# 2_MXM_Connector_1.net
KiCad netlist of a schematic drawn in Altium Designer
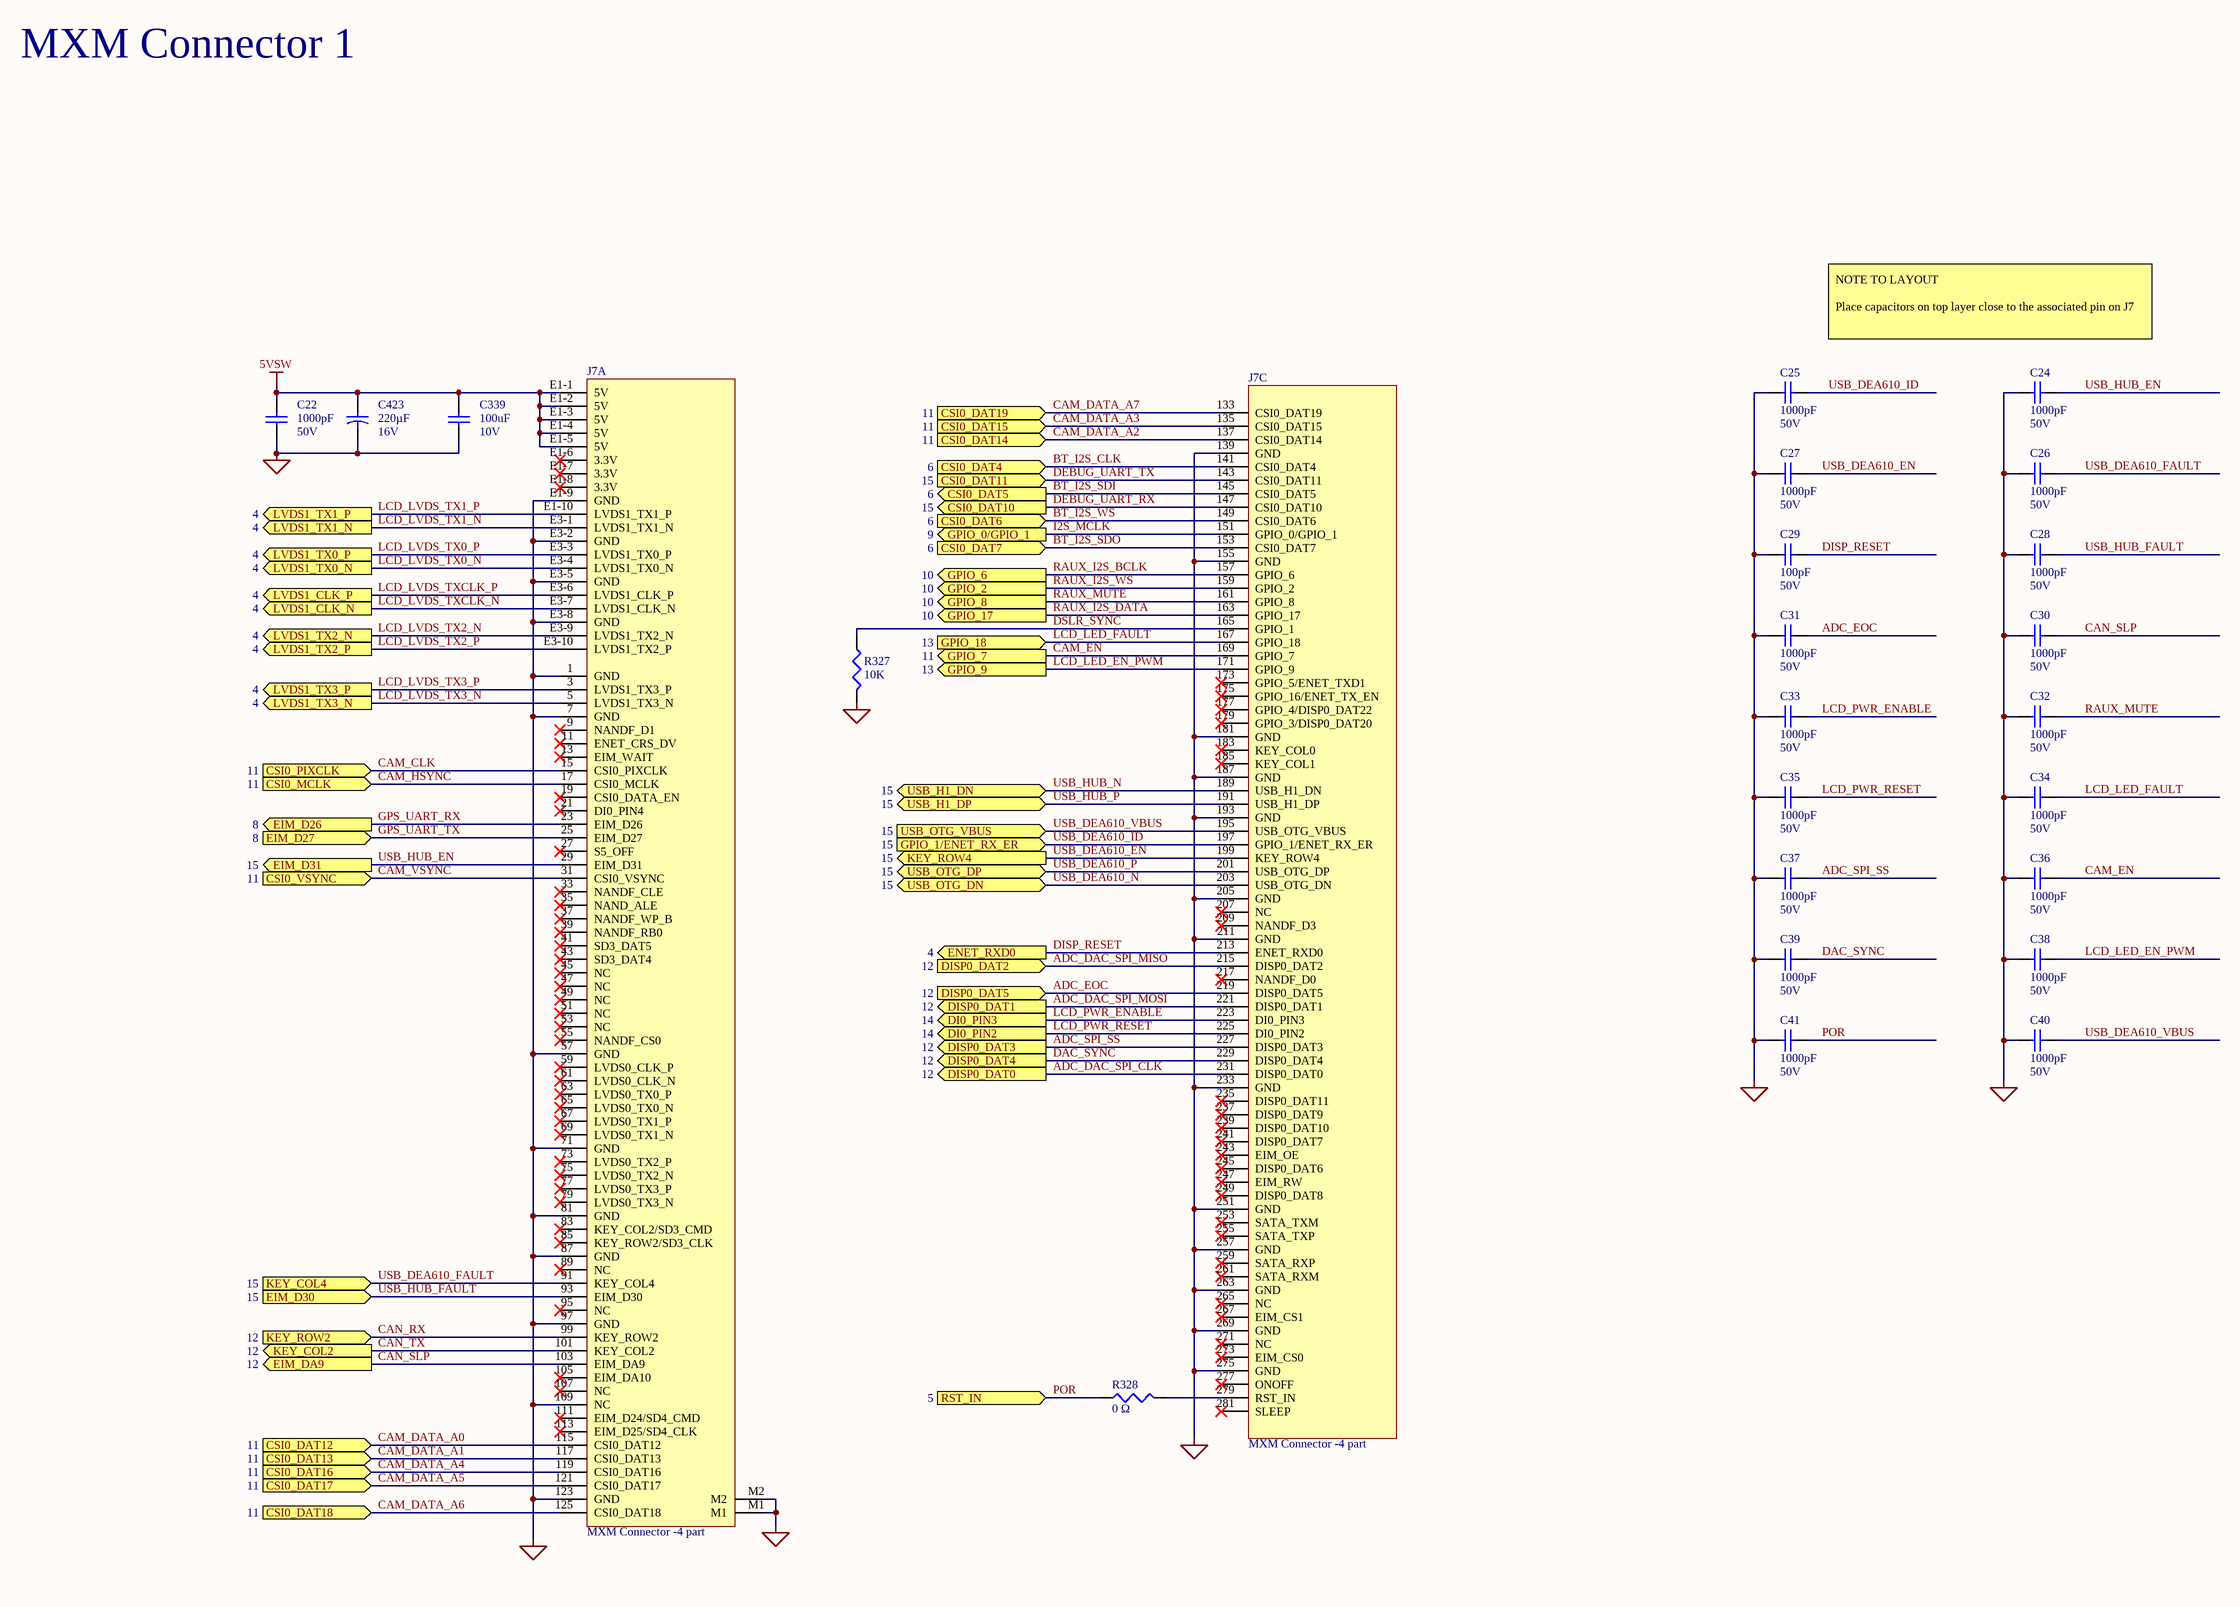
[diagram p0: 2 MXM Connector 1.SchDoc]

(export (version "E")
  (design (tool "Eeschema 10.0.6"))
  (components
    (comp (ref "C22")
      (value "1000pF")
      (footprint "CAP_0402")
      (description "Cap, Cer, 1000pF, 50V, 20%, X7R, 0402")
      (fields
        (field (name "TOLERANCE") "20%")
        (field (name "MANUFACTURER") "Murata Electronics North America")
        (field (name "VOLTAGE") "50V")
      )
      (libsource (lib "Firstview") (part "Cap 1000pF 50V 0402"))
    )
    (comp (ref "C24")
      (value "1000pF")
      (footprint "CAP_0402")
      (description "Cap, Cer, 1000pF, 50V, 20%, X7R, 0402")
      (fields
        (field (name "TOLERANCE") "20%")
        (field (name "MANUFACTURER") "Murata Electronics North America")
        (field (name "VOLTAGE") "50V")
      )
      (libsource (lib "Firstview") (part "Cap 1000pF 50V 0402"))
    )
    (comp (ref "C25")
      (value "1000pF")
      (footprint "CAP_0402")
      (description "Cap, Cer, 1000pF, 50V, 20%, X7R, 0402")
      (fields
        (field (name "TOLERANCE") "20%")
        (field (name "MANUFACTURER") "Murata Electronics North America")
        (field (name "VOLTAGE") "50V")
      )
      (libsource (lib "Firstview") (part "Cap 1000pF 50V 0402"))
    )
    (comp (ref "C26")
      (value "1000pF")
      (footprint "CAP_0402")
      (description "Cap, Cer, 1000pF, 50V, 20%, X7R, 0402")
      (fields
        (field (name "TOLERANCE") "20%")
        (field (name "MANUFACTURER") "Murata Electronics North America")
        (field (name "VOLTAGE") "50V")
      )
      (libsource (lib "Firstview") (part "Cap 1000pF 50V 0402"))
    )
    (comp (ref "C27")
      (value "1000pF")
      (footprint "CAP_0402")
      (description "Cap, Cer, 1000pF, 50V, 20%, X7R, 0402")
      (fields
        (field (name "TOLERANCE") "20%")
        (field (name "MANUFACTURER") "Murata Electronics North America")
        (field (name "VOLTAGE") "50V")
      )
      (libsource (lib "Firstview") (part "Cap 1000pF 50V 0402"))
    )
    (comp (ref "C28")
      (value "1000pF")
      (footprint "CAP_0402")
      (description "Cap, Cer, 1000pF, 50V, 20%, X7R, 0402")
      (fields
        (field (name "TOLERANCE") "20%")
        (field (name "MANUFACTURER") "Murata Electronics North America")
        (field (name "VOLTAGE") "50V")
      )
      (libsource (lib "Firstview") (part "Cap 1000pF 50V 0402"))
    )
    (comp (ref "C29")
      (value "100pF")
      (footprint "CAP_0402")
      (description "Cap, Cer, 100pF, 50V, 5%, C0G/NP0, 0402")
      (fields
        (field (name "TOLERANCE") "5%")
        (field (name "MANUFACTURER") "Yageo")
        (field (name "VOLTAGE") "50V")
      )
      (libsource (lib "Firstview") (part "Cap 100pF 50V 0402"))
    )
    (comp (ref "C30")
      (value "1000pF")
      (footprint "CAP_0402")
      (description "Cap, Cer, 1000pF, 50V, 20%, X7R, 0402")
      (fields
        (field (name "TOLERANCE") "20%")
        (field (name "MANUFACTURER") "Murata Electronics North America")
        (field (name "VOLTAGE") "50V")
      )
      (libsource (lib "Firstview") (part "Cap 1000pF 50V 0402"))
    )
    (comp (ref "C31")
      (value "1000pF")
      (footprint "CAP_0402")
      (description "Cap, Cer, 1000pF, 50V, 20%, X7R, 0402")
      (fields
        (field (name "TOLERANCE") "20%")
        (field (name "MANUFACTURER") "Murata Electronics North America")
        (field (name "VOLTAGE") "50V")
      )
      (libsource (lib "Firstview") (part "Cap 1000pF 50V 0402"))
    )
    (comp (ref "C32")
      (value "1000pF")
      (footprint "CAP_0402")
      (description "Cap, Cer, 1000pF, 50V, 20%, X7R, 0402")
      (fields
        (field (name "TOLERANCE") "20%")
        (field (name "MANUFACTURER") "Murata Electronics North America")
        (field (name "VOLTAGE") "50V")
      )
      (libsource (lib "Firstview") (part "Cap 1000pF 50V 0402"))
    )
    (comp (ref "C33")
      (value "1000pF")
      (footprint "CAP_0402")
      (description "Cap, Cer, 1000pF, 50V, 20%, X7R, 0402")
      (fields
        (field (name "TOLERANCE") "20%")
        (field (name "MANUFACTURER") "Murata Electronics North America")
        (field (name "VOLTAGE") "50V")
      )
      (libsource (lib "Firstview") (part "Cap 1000pF 50V 0402"))
    )
    (comp (ref "C34")
      (value "1000pF")
      (footprint "CAP_0402")
      (description "Cap, Cer, 1000pF, 50V, 20%, X7R, 0402")
      (fields
        (field (name "TOLERANCE") "20%")
        (field (name "MANUFACTURER") "Murata Electronics North America")
        (field (name "VOLTAGE") "50V")
      )
      (libsource (lib "Firstview") (part "Cap 1000pF 50V 0402"))
    )
    (comp (ref "C35")
      (value "1000pF")
      (footprint "CAP_0402")
      (description "Cap, Cer, 1000pF, 50V, 20%, X7R, 0402")
      (fields
        (field (name "TOLERANCE") "20%")
        (field (name "MANUFACTURER") "Murata Electronics North America")
        (field (name "VOLTAGE") "50V")
      )
      (libsource (lib "Firstview") (part "Cap 1000pF 50V 0402"))
    )
    (comp (ref "C36")
      (value "1000pF")
      (footprint "CAP_0402")
      (description "Cap, Cer, 1000pF, 50V, 20%, X7R, 0402")
      (fields
        (field (name "TOLERANCE") "20%")
        (field (name "MANUFACTURER") "Murata Electronics North America")
        (field (name "VOLTAGE") "50V")
      )
      (libsource (lib "Firstview") (part "Cap 1000pF 50V 0402"))
    )
    (comp (ref "C37")
      (value "1000pF")
      (footprint "CAP_0402")
      (description "Cap, Cer, 1000pF, 50V, 20%, X7R, 0402")
      (fields
        (field (name "TOLERANCE") "20%")
        (field (name "MANUFACTURER") "Murata Electronics North America")
        (field (name "VOLTAGE") "50V")
      )
      (libsource (lib "Firstview") (part "Cap 1000pF 50V 0402"))
    )
    (comp (ref "C38")
      (value "1000pF")
      (footprint "CAP_0402")
      (description "Cap, Cer, 1000pF, 50V, 20%, X7R, 0402")
      (fields
        (field (name "TOLERANCE") "20%")
        (field (name "MANUFACTURER") "Murata Electronics North America")
        (field (name "VOLTAGE") "50V")
      )
      (libsource (lib "Firstview") (part "Cap 1000pF 50V 0402"))
    )
    (comp (ref "C39")
      (value "1000pF")
      (footprint "CAP_0402")
      (description "Cap, Cer, 1000pF, 50V, 20%, X7R, 0402")
      (fields
        (field (name "TOLERANCE") "20%")
        (field (name "MANUFACTURER") "Murata Electronics North America")
        (field (name "VOLTAGE") "50V")
      )
      (libsource (lib "Firstview") (part "Cap 1000pF 50V 0402"))
    )
    (comp (ref "C40")
      (value "1000pF")
      (footprint "CAP_0402")
      (description "Cap, Cer, 1000pF, 50V, 20%, X7R, 0402")
      (fields
        (field (name "TOLERANCE") "20%")
        (field (name "MANUFACTURER") "Murata Electronics North America")
        (field (name "VOLTAGE") "50V")
      )
      (libsource (lib "Firstview") (part "Cap 1000pF 50V 0402"))
    )
    (comp (ref "C41")
      (value "1000pF")
      (footprint "CAP_0402")
      (description "Cap, Cer, 1000pF, 50V, 20%, X7R, 0402")
      (fields
        (field (name "TOLERANCE") "20%")
        (field (name "MANUFACTURER") "Murata Electronics North America")
        (field (name "VOLTAGE") "50V")
      )
      (libsource (lib "Firstview") (part "Cap 1000pF 50V 0402"))
    )
    (comp (ref "C339")
      (value "100uF")
      (footprint "CAP_1210")
      (description "Cap, Cer, 100uF, 10V, 20%, X5R, 1210")
      (fields
        (field (name "MANUFACTURER") "Kemet")
        (field (name "VOLTAGE") "10V")
        (field (name "Comment") "Cap 100uF 10V 1210")
      )
      (libsource (lib "Firstview") (part "Cap 100uF 10V 1210"))
    )
    (comp (ref "C423")
      (value "220µF")
      (footprint "SMD(6.6x6.6)_UWT1C221MCL1GS")
      (description "Cap, Alum, 220µF, 16V, 20%, SMD")
      (fields
        (field (name "TOLERANCE") "20%")
        (field (name "MANUFACTURER") "Nichicon")
        (field (name "VOLTAGE") "16V")
      )
      (libsource (lib "Firstview") (part "Cap 220µF 16V"))
    )
    (comp (ref "J7")
      (value "MXM Connector -4 part")
      (footprint "CON_CLE9990-0402F")
      (description "Conn, 314-pin, SOM i.MX6, SMD")
      (fields (field (name "MANUFACTURER") "SMK Electronics"))
      (libsource (lib "Firstview") (part "MXM Connector -4 part"))
    )
    (comp (ref "R327")
      (value "10K")
      (footprint "RES_0402")
      (description "Res, 10K, 1/16W, 1%, 0402")
      (fields (field (name "MANUFACTURER") "Yageo") (field (name "Comment") "Res 10K 0.063W"))
      (libsource (lib "Firstview") (part "Res 10K 0.063W"))
    )
    (comp (ref "R328")
      (value "0 Ω")
      (footprint "RES_0402")
      (description "Res, 0 ohm, 1/16W, 0402")
      (fields (field (name "MANUFACTURER") "Vishay Dale") (field (name "Comment") "Res 0 ohm 0.1W"))
      (libsource (lib "Firstview") (part "Res 0 ohm 0.1W"))
    )
  )
  (nets
    (net (code "1") (name "/ADC_DAC_SPI_CLK") (class "Default")
      (node (ref "J7") (pin "231") (pinfunction "DISP0_DAT0_231") (pintype "passive"))
    )
    (net (code "2") (name "/ADC_DAC_SPI_MISO") (class "Default")
      (node (ref "J7") (pin "215") (pinfunction "DISP0_DAT2_215") (pintype "passive"))
    )
    (net (code "3") (name "/ADC_DAC_SPI_MOSI") (class "Default")
      (node (ref "J7") (pin "221") (pinfunction "DISP0_DAT1_221") (pintype "passive"))
    )
    (net (code "4") (name "/ADC_EOC") (class "Default")
      (node (ref "C31") (pin "1") (pinfunction "1_1") (pintype "passive"))
      (node (ref "J7") (pin "219") (pinfunction "DISP0_DAT5_219") (pintype "passive"))
    )
    (net (code "5") (name "/ADC_SPI_SS") (class "Default")
      (node (ref "C37") (pin "1") (pinfunction "1_1") (pintype "passive"))
      (node (ref "J7") (pin "227") (pinfunction "DISP0_DAT3_227") (pintype "passive"))
    )
    (net (code "6") (name "/BT_I2S_CLK") (class "Default")
      (node (ref "J7") (pin "141") (pinfunction "CSI0_DAT4_141") (pintype "passive"))
    )
    (net (code "7") (name "/BT_I2S_SDI") (class "Default")
      (node (ref "J7") (pin "145") (pinfunction "CSI0_DAT5_145") (pintype "passive"))
    )
    (net (code "8") (name "/BT_I2S_SDO") (class "Default")
      (node (ref "J7") (pin "153") (pinfunction "CSI0_DAT7_153") (pintype "passive"))
    )
    (net (code "9") (name "/BT_I2S_WS") (class "Default")
      (node (ref "J7") (pin "149") (pinfunction "CSI0_DAT6_149") (pintype "passive"))
    )
    (net (code "10") (name "/CAM_CLK") (class "Default")
      (node (ref "J7") (pin "15") (pinfunction "CSI0_PIXCLK_15") (pintype "passive"))
    )
    (net (code "11") (name "/CAM_DATA_A0") (class "Default")
      (node (ref "J7") (pin "115") (pinfunction "CSI0_DAT12_115") (pintype "passive"))
    )
    (net (code "12") (name "/CAM_DATA_A1") (class "Default")
      (node (ref "J7") (pin "117") (pinfunction "CSI0_DAT13_117") (pintype "passive"))
    )
    (net (code "13") (name "/CAM_DATA_A2") (class "Default")
      (node (ref "J7") (pin "137") (pinfunction "CSI0_DAT14_137") (pintype "passive"))
    )
    (net (code "14") (name "/CAM_DATA_A3") (class "Default")
      (node (ref "J7") (pin "135") (pinfunction "CSI0_DAT15_135") (pintype "passive"))
    )
    (net (code "15") (name "/CAM_DATA_A4") (class "Default")
      (node (ref "J7") (pin "119") (pinfunction "CSI0_DAT16_119") (pintype "passive"))
    )
    (net (code "16") (name "/CAM_DATA_A5") (class "Default")
      (node (ref "J7") (pin "121") (pinfunction "CSI0_DAT17_121") (pintype "passive"))
    )
    (net (code "17") (name "/CAM_DATA_A6") (class "Default")
      (node (ref "J7") (pin "125") (pinfunction "CSI0_DAT18_125") (pintype "passive"))
    )
    (net (code "18") (name "/CAM_DATA_A7") (class "Default")
      (node (ref "J7") (pin "133") (pinfunction "CSI0_DAT19_133") (pintype "passive"))
    )
    (net (code "19") (name "/CAM_EN") (class "Default")
      (node (ref "C36") (pin "1") (pinfunction "1_1") (pintype "passive"))
      (node (ref "J7") (pin "169") (pinfunction "GPIO_7_169") (pintype "passive"))
    )
    (net (code "20") (name "/CAM_HSYNC") (class "Default")
      (node (ref "J7") (pin "17") (pinfunction "CSI0_MCLK_17") (pintype "passive"))
    )
    (net (code "21") (name "/CAM_VSYNC") (class "Default")
      (node (ref "J7") (pin "31") (pinfunction "CSI0_VSYNC_31") (pintype "passive"))
    )
    (net (code "22") (name "/CAN_RX") (class "Default")
      (node (ref "J7") (pin "99") (pinfunction "KEY_ROW2_99") (pintype "passive"))
    )
    (net (code "23") (name "/CAN_SLP") (class "Default")
      (node (ref "C30") (pin "1") (pinfunction "1_1") (pintype "passive"))
      (node (ref "J7") (pin "103") (pinfunction "EIM_DA9_103") (pintype "passive"))
    )
    (net (code "24") (name "/CAN_TX") (class "Default")
      (node (ref "J7") (pin "101") (pinfunction "KEY_COL2_101") (pintype "passive"))
    )
    (net (code "25") (name "/DAC_SYNC") (class "Default")
      (node (ref "C39") (pin "1") (pinfunction "1_1") (pintype "passive"))
      (node (ref "J7") (pin "229") (pinfunction "DISP0_DAT4_229") (pintype "passive"))
    )
    (net (code "26") (name "/DEBUG_UART_RX") (class "Default")
      (node (ref "J7") (pin "147") (pinfunction "CSI0_DAT10_147") (pintype "passive"))
    )
    (net (code "27") (name "/DEBUG_UART_TX") (class "Default")
      (node (ref "J7") (pin "143") (pinfunction "CSI0_DAT11_143") (pintype "passive"))
    )
    (net (code "28") (name "/DISP_RESET") (class "Default")
      (node (ref "C29") (pin "1") (pinfunction "1_1") (pintype "passive"))
      (node (ref "J7") (pin "213") (pinfunction "ENET_RXD0_213") (pintype "passive"))
    )
    (net (code "29") (name "/DSLR_SYNC") (class "Default")
      (node (ref "J7") (pin "165") (pinfunction "GPIO_1_165") (pintype "passive"))
      (node (ref "R327") (pin "1") (pinfunction "1_1") (pintype "passive"))
    )
    (net (code "30") (name "/GPS_UART_RX") (class "Default")
      (node (ref "J7") (pin "23") (pinfunction "EIM_D26_23") (pintype "passive"))
    )
    (net (code "31") (name "/GPS_UART_TX") (class "Default")
      (node (ref "J7") (pin "25") (pinfunction "EIM_D27_25") (pintype "passive"))
    )
    (net (code "32") (name "/I2S_MCLK") (class "Default")
      (node (ref "J7") (pin "151") (pinfunction "GPIO_0/GPIO_1_151") (pintype "passive"))
    )
    (net (code "33") (name "/LCD_LED_EN_PWM") (class "Default")
      (node (ref "C38") (pin "1") (pinfunction "1_1") (pintype "passive"))
      (node (ref "J7") (pin "171") (pinfunction "GPIO_9_171") (pintype "passive"))
    )
    (net (code "34") (name "/LCD_LED_FAULT") (class "Default")
      (node (ref "C34") (pin "1") (pinfunction "1_1") (pintype "passive"))
      (node (ref "J7") (pin "167") (pinfunction "GPIO_18_167") (pintype "passive"))
    )
    (net (code "35") (name "/LCD_LVDS_TX0_N") (class "Default")
      (node (ref "J7") (pin "E3-4") (pinfunction "LVDS1_TX0_N_E3-4") (pintype "passive"))
    )
    (net (code "36") (name "/LCD_LVDS_TX0_P") (class "Default")
      (node (ref "J7") (pin "E3-3") (pinfunction "LVDS1_TX0_P_E3-3") (pintype "passive"))
    )
    (net (code "37") (name "/LCD_LVDS_TX1_N") (class "Default")
      (node (ref "J7") (pin "E3-1") (pinfunction "LVDS1_TX1_N_E3-1") (pintype "passive"))
    )
    (net (code "38") (name "/LCD_LVDS_TX1_P") (class "Default")
      (node (ref "J7") (pin "E1-10") (pinfunction "LVDS1_TX1_P_E1-10") (pintype "passive"))
    )
    (net (code "39") (name "/LCD_LVDS_TX2_N") (class "Default")
      (node (ref "J7") (pin "E3-9") (pinfunction "LVDS1_TX2_N_E3-9") (pintype "passive"))
    )
    (net (code "40") (name "/LCD_LVDS_TX2_P") (class "Default")
      (node (ref "J7") (pin "E3-10") (pinfunction "LVDS1_TX2_P_E3-10") (pintype "passive"))
    )
    (net (code "41") (name "/LCD_LVDS_TX3_N") (class "Default")
      (node (ref "J7") (pin "5") (pinfunction "LVDS1_TX3_N_5") (pintype "passive"))
    )
    (net (code "42") (name "/LCD_LVDS_TX3_P") (class "Default")
      (node (ref "J7") (pin "3") (pinfunction "LVDS1_TX3_P_3") (pintype "passive"))
    )
    (net (code "43") (name "/LCD_LVDS_TXCLK_N") (class "Default")
      (node (ref "J7") (pin "E3-7") (pinfunction "LVDS1_CLK_N_E3-7") (pintype "passive"))
    )
    (net (code "44") (name "/LCD_LVDS_TXCLK_P") (class "Default")
      (node (ref "J7") (pin "E3-6") (pinfunction "LVDS1_CLK_P_E3-6") (pintype "passive"))
    )
    (net (code "45") (name "/LCD_PWR_ENABLE") (class "Default")
      (node (ref "C33") (pin "1") (pinfunction "1_1") (pintype "passive"))
      (node (ref "J7") (pin "223") (pinfunction "DI0_PIN3_223") (pintype "passive"))
    )
    (net (code "46") (name "/LCD_PWR_RESET") (class "Default")
      (node (ref "C35") (pin "1") (pinfunction "1_1") (pintype "passive"))
      (node (ref "J7") (pin "225") (pinfunction "DI0_PIN2_225") (pintype "passive"))
    )
    (net (code "47") (name "/POR") (class "Default")
      (node (ref "C41") (pin "1") (pinfunction "1_1") (pintype "passive"))
      (node (ref "R328") (pin "1") (pinfunction "1_1") (pintype "passive"))
    )
    (net (code "48") (name "/RAUX_I2S_BCLK") (class "Default")
      (node (ref "J7") (pin "157") (pinfunction "GPIO_6_157") (pintype "passive"))
    )
    (net (code "49") (name "/RAUX_I2S_DATA") (class "Default")
      (node (ref "J7") (pin "163") (pinfunction "GPIO_17_163") (pintype "passive"))
    )
    (net (code "50") (name "/RAUX_I2S_WS") (class "Default")
      (node (ref "J7") (pin "159") (pinfunction "GPIO_2_159") (pintype "passive"))
    )
    (net (code "51") (name "/RAUX_MUTE") (class "Default")
      (node (ref "C32") (pin "1") (pinfunction "1_1") (pintype "passive"))
      (node (ref "J7") (pin "161") (pinfunction "GPIO_8_161") (pintype "passive"))
    )
    (net (code "52") (name "/USB_DEA610_EN") (class "Default")
      (node (ref "C27") (pin "1") (pinfunction "1_1") (pintype "passive"))
      (node (ref "J7") (pin "199") (pinfunction "KEY_ROW4_199") (pintype "passive"))
    )
    (net (code "53") (name "/USB_DEA610_FAULT") (class "Default")
      (node (ref "C26") (pin "1") (pinfunction "1_1") (pintype "passive"))
      (node (ref "J7") (pin "91") (pinfunction "KEY_COL4_91") (pintype "passive"))
    )
    (net (code "54") (name "/USB_DEA610_ID") (class "Default")
      (node (ref "C25") (pin "1") (pinfunction "1_1") (pintype "passive"))
      (node (ref "J7") (pin "197") (pinfunction "GPIO_1/ENET_RX_ER_197") (pintype "passive"))
    )
    (net (code "55") (name "/USB_DEA610_N") (class "Default")
      (node (ref "J7") (pin "203") (pinfunction "USB_OTG_DN_203") (pintype "passive"))
    )
    (net (code "56") (name "/USB_DEA610_P") (class "Default")
      (node (ref "J7") (pin "201") (pinfunction "USB_OTG_DP_201") (pintype "passive"))
    )
    (net (code "57") (name "/USB_DEA610_VBUS") (class "Default")
      (node (ref "C40") (pin "1") (pinfunction "1_1") (pintype "passive"))
      (node (ref "J7") (pin "195") (pinfunction "USB_OTG_VBUS_195") (pintype "passive"))
    )
    (net (code "58") (name "/USB_HUB_EN") (class "Default")
      (node (ref "C24") (pin "1") (pinfunction "1_1") (pintype "passive"))
      (node (ref "J7") (pin "29") (pinfunction "EIM_D31_29") (pintype "passive"))
    )
    (net (code "59") (name "/USB_HUB_FAULT") (class "Default")
      (node (ref "C28") (pin "1") (pinfunction "1_1") (pintype "passive"))
      (node (ref "J7") (pin "93") (pinfunction "EIM_D30_93") (pintype "passive"))
    )
    (net (code "60") (name "/USB_HUB_N") (class "Default")
      (node (ref "J7") (pin "189") (pinfunction "USB_H1_DN_189") (pintype "passive"))
    )
    (net (code "61") (name "/USB_HUB_P") (class "Default")
      (node (ref "J7") (pin "191") (pinfunction "USB_H1_DP_191") (pintype "passive"))
    )
    (net (code "62") (name "5VSW") (class "Default")
      (node (ref "C22") (pin "1") (pinfunction "1_1") (pintype "passive"))
      (node (ref "C339") (pin "1") (pinfunction "1_1") (pintype "passive"))
      (node (ref "C423") (pin "1") (pinfunction "1_1") (pintype "passive"))
      (node (ref "J7") (pin "E1-1") (pinfunction "5V_E1-1") (pintype "passive"))
      (node (ref "J7") (pin "E1-2") (pinfunction "5V_E1-2") (pintype "passive"))
      (node (ref "J7") (pin "E1-3") (pinfunction "5V_E1-3") (pintype "passive"))
      (node (ref "J7") (pin "E1-4") (pinfunction "5V_E1-4") (pintype "passive"))
      (node (ref "J7") (pin "E1-5") (pinfunction "5V_E1-5") (pintype "passive"))
    )
    (net (code "63") (name "GND") (class "Default")
      (node (ref "C22") (pin "2") (pinfunction "2_2") (pintype "passive"))
      (node (ref "C24") (pin "2") (pinfunction "2_2") (pintype "passive"))
      (node (ref "C25") (pin "2") (pinfunction "2_2") (pintype "passive"))
      (node (ref "C26") (pin "2") (pinfunction "2_2") (pintype "passive"))
      (node (ref "C27") (pin "2") (pinfunction "2_2") (pintype "passive"))
      (node (ref "C28") (pin "2") (pinfunction "2_2") (pintype "passive"))
      (node (ref "C29") (pin "2") (pinfunction "2_2") (pintype "passive"))
      (node (ref "C30") (pin "2") (pinfunction "2_2") (pintype "passive"))
      (node (ref "C31") (pin "2") (pinfunction "2_2") (pintype "passive"))
      (node (ref "C32") (pin "2") (pinfunction "2_2") (pintype "passive"))
      (node (ref "C33") (pin "2") (pinfunction "2_2") (pintype "passive"))
      (node (ref "C339") (pin "2") (pinfunction "2_2") (pintype "passive"))
      (node (ref "C34") (pin "2") (pinfunction "2_2") (pintype "passive"))
      (node (ref "C35") (pin "2") (pinfunction "2_2") (pintype "passive"))
      (node (ref "C36") (pin "2") (pinfunction "2_2") (pintype "passive"))
      (node (ref "C37") (pin "2") (pinfunction "2_2") (pintype "passive"))
      (node (ref "C38") (pin "2") (pinfunction "2_2") (pintype "passive"))
      (node (ref "C39") (pin "2") (pinfunction "2_2") (pintype "passive"))
      (node (ref "C40") (pin "2") (pinfunction "2_2") (pintype "passive"))
      (node (ref "C41") (pin "2") (pinfunction "2_2") (pintype "passive"))
      (node (ref "C423") (pin "2") (pinfunction "2_2") (pintype "passive"))
      (node (ref "J7") (pin "1") (pinfunction "GND_1") (pintype "passive"))
      (node (ref "J7") (pin "109") (pinfunction "NC_109") (pintype "passive"))
      (node (ref "J7") (pin "123") (pinfunction "GND_123") (pintype "passive"))
      (node (ref "J7") (pin "139") (pinfunction "GND_139") (pintype "passive"))
      (node (ref "J7") (pin "155") (pinfunction "GND_155") (pintype "passive"))
      (node (ref "J7") (pin "181") (pinfunction "GND_181") (pintype "passive"))
      (node (ref "J7") (pin "187") (pinfunction "GND_187") (pintype "passive"))
      (node (ref "J7") (pin "193") (pinfunction "GND_193") (pintype "passive"))
      (node (ref "J7") (pin "205") (pinfunction "GND_205") (pintype "passive"))
      (node (ref "J7") (pin "211") (pinfunction "GND_211") (pintype "passive"))
      (node (ref "J7") (pin "233") (pinfunction "GND_233") (pintype "passive"))
      (node (ref "J7") (pin "251") (pinfunction "GND_251") (pintype "passive"))
      (node (ref "J7") (pin "257") (pinfunction "GND_257") (pintype "passive"))
      (node (ref "J7") (pin "263") (pinfunction "GND_263") (pintype "passive"))
      (node (ref "J7") (pin "269") (pinfunction "GND_269") (pintype "passive"))
      (node (ref "J7") (pin "275") (pinfunction "GND_275") (pintype "passive"))
      (node (ref "J7") (pin "57") (pinfunction "GND_57") (pintype "passive"))
      (node (ref "J7") (pin "7") (pinfunction "GND_7") (pintype "passive"))
      (node (ref "J7") (pin "71") (pinfunction "GND_71") (pintype "passive"))
      (node (ref "J7") (pin "81") (pinfunction "GND_81") (pintype "passive"))
      (node (ref "J7") (pin "87") (pinfunction "GND_87") (pintype "passive"))
      (node (ref "J7") (pin "97") (pinfunction "GND_97") (pintype "passive"))
      (node (ref "J7") (pin "E1-9") (pinfunction "GND_E1-9") (pintype "passive"))
      (node (ref "J7") (pin "E3-2") (pinfunction "GND_E3-2") (pintype "passive"))
      (node (ref "J7") (pin "E3-5") (pinfunction "GND_E3-5") (pintype "passive"))
      (node (ref "J7") (pin "E3-8") (pinfunction "GND_E3-8") (pintype "passive"))
      (node (ref "J7") (pin "M1") (pinfunction "M1_M1") (pintype "passive"))
      (node (ref "J7") (pin "M2") (pinfunction "M2_M2") (pintype "passive"))
      (node (ref "R327") (pin "2") (pinfunction "2_2") (pintype "passive"))
    )
    (net (code "64") (name "Net-(J7C-RST_IN)") (class "Default")
      (node (ref "J7") (pin "279") (pinfunction "RST_IN_279") (pintype "passive"))
      (node (ref "R328") (pin "2") (pinfunction "2_2") (pintype "passive"))
    )
    (net (code "65") (name "unconnected-(J7A-3.3V-PadE1-6)") (class "Default")
      (node (ref "J7") (pin "E1-6") (pinfunction "3.3V_E1-6") (pintype "passive+no_connect"))
    )
    (net (code "66") (name "unconnected-(J7A-3.3V-PadE1-7)") (class "Default")
      (node (ref "J7") (pin "E1-7") (pinfunction "3.3V_E1-7") (pintype "passive+no_connect"))
    )
    (net (code "67") (name "unconnected-(J7A-3.3V-PadE1-8)") (class "Default")
      (node (ref "J7") (pin "E1-8") (pinfunction "3.3V_E1-8") (pintype "passive+no_connect"))
    )
    (net (code "68") (name "unconnected-(J7A-CSI0_DATA_EN-Pad19)") (class "Default")
      (node (ref "J7") (pin "19") (pinfunction "CSI0_DATA_EN_19") (pintype "passive+no_connect"))
    )
    (net (code "69") (name "unconnected-(J7A-DI0_PIN4-Pad21)") (class "Default")
      (node (ref "J7") (pin "21") (pinfunction "DI0_PIN4_21") (pintype "passive+no_connect"))
    )
    (net (code "70") (name "unconnected-(J7A-EIM_D24{slash}SD4_CMD-Pad111)") (class "Default")
      (node (ref "J7") (pin "111") (pinfunction "EIM_D24/SD4_CMD_111") (pintype "passive+no_connect"))
    )
    (net (code "71") (name "unconnected-(J7A-EIM_D25{slash}SD4_CLK-Pad113)") (class "Default")
      (node (ref "J7") (pin "113") (pinfunction "EIM_D25/SD4_CLK_113") (pintype "passive+no_connect"))
    )
    (net (code "72") (name "unconnected-(J7A-EIM_DA10-Pad105)") (class "Default")
      (node (ref "J7") (pin "105") (pinfunction "EIM_DA10_105") (pintype "passive+no_connect"))
    )
    (net (code "73") (name "unconnected-(J7A-EIM_WAIT-Pad13)") (class "Default")
      (node (ref "J7") (pin "13") (pinfunction "EIM_WAIT_13") (pintype "passive+no_connect"))
    )
    (net (code "74") (name "unconnected-(J7A-ENET_CRS_DV-Pad11)") (class "Default")
      (node (ref "J7") (pin "11") (pinfunction "ENET_CRS_DV_11") (pintype "passive+no_connect"))
    )
    (net (code "75") (name "unconnected-(J7A-KEY_COL2{slash}SD3_CMD-Pad83)") (class "Default")
      (node (ref "J7") (pin "83") (pinfunction "KEY_COL2/SD3_CMD_83") (pintype "passive+no_connect"))
    )
    (net (code "76") (name "unconnected-(J7A-KEY_ROW2{slash}SD3_CLK-Pad85)") (class "Default")
      (node (ref "J7") (pin "85") (pinfunction "KEY_ROW2/SD3_CLK_85") (pintype "passive+no_connect"))
    )
    (net (code "77") (name "unconnected-(J7A-LVDS0_CLK_N-Pad61)") (class "Default")
      (node (ref "J7") (pin "61") (pinfunction "LVDS0_CLK_N_61") (pintype "passive+no_connect"))
    )
    (net (code "78") (name "unconnected-(J7A-LVDS0_CLK_P-Pad59)") (class "Default")
      (node (ref "J7") (pin "59") (pinfunction "LVDS0_CLK_P_59") (pintype "passive+no_connect"))
    )
    (net (code "79") (name "unconnected-(J7A-LVDS0_TX0_N-Pad65)") (class "Default")
      (node (ref "J7") (pin "65") (pinfunction "LVDS0_TX0_N_65") (pintype "passive+no_connect"))
    )
    (net (code "80") (name "unconnected-(J7A-LVDS0_TX0_P-Pad63)") (class "Default")
      (node (ref "J7") (pin "63") (pinfunction "LVDS0_TX0_P_63") (pintype "passive+no_connect"))
    )
    (net (code "81") (name "unconnected-(J7A-LVDS0_TX1_N-Pad69)") (class "Default")
      (node (ref "J7") (pin "69") (pinfunction "LVDS0_TX1_N_69") (pintype "passive+no_connect"))
    )
    (net (code "82") (name "unconnected-(J7A-LVDS0_TX1_P-Pad67)") (class "Default")
      (node (ref "J7") (pin "67") (pinfunction "LVDS0_TX1_P_67") (pintype "passive+no_connect"))
    )
    (net (code "83") (name "unconnected-(J7A-LVDS0_TX2_N-Pad75)") (class "Default")
      (node (ref "J7") (pin "75") (pinfunction "LVDS0_TX2_N_75") (pintype "passive+no_connect"))
    )
    (net (code "84") (name "unconnected-(J7A-LVDS0_TX2_P-Pad73)") (class "Default")
      (node (ref "J7") (pin "73") (pinfunction "LVDS0_TX2_P_73") (pintype "passive+no_connect"))
    )
    (net (code "85") (name "unconnected-(J7A-LVDS0_TX3_N-Pad79)") (class "Default")
      (node (ref "J7") (pin "79") (pinfunction "LVDS0_TX3_N_79") (pintype "passive+no_connect"))
    )
    (net (code "86") (name "unconnected-(J7A-LVDS0_TX3_P-Pad77)") (class "Default")
      (node (ref "J7") (pin "77") (pinfunction "LVDS0_TX3_P_77") (pintype "passive+no_connect"))
    )
    (net (code "87") (name "unconnected-(J7A-NANDF_CLE-Pad33)") (class "Default")
      (node (ref "J7") (pin "33") (pinfunction "NANDF_CLE_33") (pintype "passive+no_connect"))
    )
    (net (code "88") (name "unconnected-(J7A-NANDF_CS0-Pad55)") (class "Default")
      (node (ref "J7") (pin "55") (pinfunction "NANDF_CS0_55") (pintype "passive+no_connect"))
    )
    (net (code "89") (name "unconnected-(J7A-NANDF_D1-Pad9)") (class "Default")
      (node (ref "J7") (pin "9") (pinfunction "NANDF_D1_9") (pintype "passive+no_connect"))
    )
    (net (code "90") (name "unconnected-(J7A-NANDF_RB0-Pad39)") (class "Default")
      (node (ref "J7") (pin "39") (pinfunction "NANDF_RB0_39") (pintype "passive+no_connect"))
    )
    (net (code "91") (name "unconnected-(J7A-NANDF_WP_B-Pad37)") (class "Default")
      (node (ref "J7") (pin "37") (pinfunction "NANDF_WP_B_37") (pintype "passive+no_connect"))
    )
    (net (code "92") (name "unconnected-(J7A-NAND_ALE-Pad35)") (class "Default")
      (node (ref "J7") (pin "35") (pinfunction "NAND_ALE_35") (pintype "passive+no_connect"))
    )
    (net (code "93") (name "unconnected-(J7A-NC-Pad45)") (class "Default")
      (node (ref "J7") (pin "45") (pinfunction "NC_45") (pintype "passive+no_connect"))
    )
    (net (code "94") (name "unconnected-(J7A-NC-Pad47)") (class "Default")
      (node (ref "J7") (pin "47") (pinfunction "NC_47") (pintype "passive+no_connect"))
    )
    (net (code "95") (name "unconnected-(J7A-NC-Pad49)") (class "Default")
      (node (ref "J7") (pin "49") (pinfunction "NC_49") (pintype "passive+no_connect"))
    )
    (net (code "96") (name "unconnected-(J7A-NC-Pad51)") (class "Default")
      (node (ref "J7") (pin "51") (pinfunction "NC_51") (pintype "passive+no_connect"))
    )
    (net (code "97") (name "unconnected-(J7A-NC-Pad53)") (class "Default")
      (node (ref "J7") (pin "53") (pinfunction "NC_53") (pintype "passive+no_connect"))
    )
    (net (code "98") (name "unconnected-(J7A-NC-Pad89)") (class "Default")
      (node (ref "J7") (pin "89") (pinfunction "NC_89") (pintype "passive+no_connect"))
    )
    (net (code "99") (name "unconnected-(J7A-NC-Pad95)") (class "Default")
      (node (ref "J7") (pin "95") (pinfunction "NC_95") (pintype "passive+no_connect"))
    )
    (net (code "100") (name "unconnected-(J7A-NC-Pad107)") (class "Default")
      (node (ref "J7") (pin "107") (pinfunction "NC_107") (pintype "passive+no_connect"))
    )
    (net (code "101") (name "unconnected-(J7A-S5_OFF-Pad27)") (class "Default")
      (node (ref "J7") (pin "27") (pinfunction "S5_OFF_27") (pintype "passive+no_connect"))
    )
    (net (code "102") (name "unconnected-(J7A-SD3_DAT4-Pad43)") (class "Default")
      (node (ref "J7") (pin "43") (pinfunction "SD3_DAT4_43") (pintype "passive+no_connect"))
    )
    (net (code "103") (name "unconnected-(J7A-SD3_DAT5-Pad41)") (class "Default")
      (node (ref "J7") (pin "41") (pinfunction "SD3_DAT5_41") (pintype "passive+no_connect"))
    )
    (net (code "104") (name "unconnected-(J7C-DISP0_DAT6-Pad245)") (class "Default")
      (node (ref "J7") (pin "245") (pinfunction "DISP0_DAT6_245") (pintype "passive+no_connect"))
    )
    (net (code "105") (name "unconnected-(J7C-DISP0_DAT7-Pad241)") (class "Default")
      (node (ref "J7") (pin "241") (pinfunction "DISP0_DAT7_241") (pintype "passive+no_connect"))
    )
    (net (code "106") (name "unconnected-(J7C-DISP0_DAT8-Pad249)") (class "Default")
      (node (ref "J7") (pin "249") (pinfunction "DISP0_DAT8_249") (pintype "passive+no_connect"))
    )
    (net (code "107") (name "unconnected-(J7C-DISP0_DAT9-Pad237)") (class "Default")
      (node (ref "J7") (pin "237") (pinfunction "DISP0_DAT9_237") (pintype "passive+no_connect"))
    )
    (net (code "108") (name "unconnected-(J7C-DISP0_DAT10-Pad239)") (class "Default")
      (node (ref "J7") (pin "239") (pinfunction "DISP0_DAT10_239") (pintype "passive+no_connect"))
    )
    (net (code "109") (name "unconnected-(J7C-DISP0_DAT11-Pad235)") (class "Default")
      (node (ref "J7") (pin "235") (pinfunction "DISP0_DAT11_235") (pintype "passive+no_connect"))
    )
    (net (code "110") (name "unconnected-(J7C-EIM_CS0-Pad273)") (class "Default")
      (node (ref "J7") (pin "273") (pinfunction "EIM_CS0_273") (pintype "passive+no_connect"))
    )
    (net (code "111") (name "unconnected-(J7C-EIM_CS1-Pad267)") (class "Default")
      (node (ref "J7") (pin "267") (pinfunction "EIM_CS1_267") (pintype "passive+no_connect"))
    )
    (net (code "112") (name "unconnected-(J7C-EIM_OE-Pad243)") (class "Default")
      (node (ref "J7") (pin "243") (pinfunction "EIM_OE_243") (pintype "passive+no_connect"))
    )
    (net (code "113") (name "unconnected-(J7C-EIM_RW-Pad247)") (class "Default")
      (node (ref "J7") (pin "247") (pinfunction "EIM_RW_247") (pintype "passive+no_connect"))
    )
    (net (code "114") (name "unconnected-(J7C-GPIO_3{slash}DISP0_DAT20-Pad179)") (class "Default")
      (node (ref "J7") (pin "179") (pinfunction "GPIO_3/DISP0_DAT20_179") (pintype "passive+no_connect"))
    )
    (net (code "115") (name "unconnected-(J7C-GPIO_4{slash}DISP0_DAT22-Pad177)") (class "Default")
      (node (ref "J7") (pin "177") (pinfunction "GPIO_4/DISP0_DAT22_177") (pintype "passive+no_connect"))
    )
    (net (code "116") (name "unconnected-(J7C-GPIO_5{slash}ENET_TXD1-Pad173)") (class "Default")
      (node (ref "J7") (pin "173") (pinfunction "GPIO_5/ENET_TXD1_173") (pintype "passive+no_connect"))
    )
    (net (code "117") (name "unconnected-(J7C-GPIO_16{slash}ENET_TX_EN-Pad175)") (class "Default")
      (node (ref "J7") (pin "175") (pinfunction "GPIO_16/ENET_TX_EN_175") (pintype "passive+no_connect"))
    )
    (net (code "118") (name "unconnected-(J7C-KEY_COL0-Pad183)") (class "Default")
      (node (ref "J7") (pin "183") (pinfunction "KEY_COL0_183") (pintype "passive+no_connect"))
    )
    (net (code "119") (name "unconnected-(J7C-KEY_COL1-Pad185)") (class "Default")
      (node (ref "J7") (pin "185") (pinfunction "KEY_COL1_185") (pintype "passive+no_connect"))
    )
    (net (code "120") (name "unconnected-(J7C-NANDF_D0-Pad217)") (class "Default")
      (node (ref "J7") (pin "217") (pinfunction "NANDF_D0_217") (pintype "passive+no_connect"))
    )
    (net (code "121") (name "unconnected-(J7C-NANDF_D3-Pad209)") (class "Default")
      (node (ref "J7") (pin "209") (pinfunction "NANDF_D3_209") (pintype "passive+no_connect"))
    )
    (net (code "122") (name "unconnected-(J7C-NC-Pad207)") (class "Default")
      (node (ref "J7") (pin "207") (pinfunction "NC_207") (pintype "passive+no_connect"))
    )
    (net (code "123") (name "unconnected-(J7C-NC-Pad265)") (class "Default")
      (node (ref "J7") (pin "265") (pinfunction "NC_265") (pintype "passive+no_connect"))
    )
    (net (code "124") (name "unconnected-(J7C-NC-Pad271)") (class "Default")
      (node (ref "J7") (pin "271") (pinfunction "NC_271") (pintype "passive+no_connect"))
    )
    (net (code "125") (name "unconnected-(J7C-ONOFF-Pad277)") (class "Default")
      (node (ref "J7") (pin "277") (pinfunction "ONOFF_277") (pintype "passive+no_connect"))
    )
    (net (code "126") (name "unconnected-(J7C-SATA_RXM-Pad261)") (class "Default")
      (node (ref "J7") (pin "261") (pinfunction "SATA_RXM_261") (pintype "passive+no_connect"))
    )
    (net (code "127") (name "unconnected-(J7C-SATA_RXP-Pad259)") (class "Default")
      (node (ref "J7") (pin "259") (pinfunction "SATA_RXP_259") (pintype "passive+no_connect"))
    )
    (net (code "128") (name "unconnected-(J7C-SATA_TXM-Pad253)") (class "Default")
      (node (ref "J7") (pin "253") (pinfunction "SATA_TXM_253") (pintype "passive+no_connect"))
    )
    (net (code "129") (name "unconnected-(J7C-SATA_TXP-Pad255)") (class "Default")
      (node (ref "J7") (pin "255") (pinfunction "SATA_TXP_255") (pintype "passive+no_connect"))
    )
    (net (code "130") (name "unconnected-(J7C-SLEEP-Pad281)") (class "Default")
      (node (ref "J7") (pin "281") (pinfunction "SLEEP_281") (pintype "passive+no_connect"))
    )
  )
)
